# design.net
KiCad netlist of a schematic drawn in Altium Designer
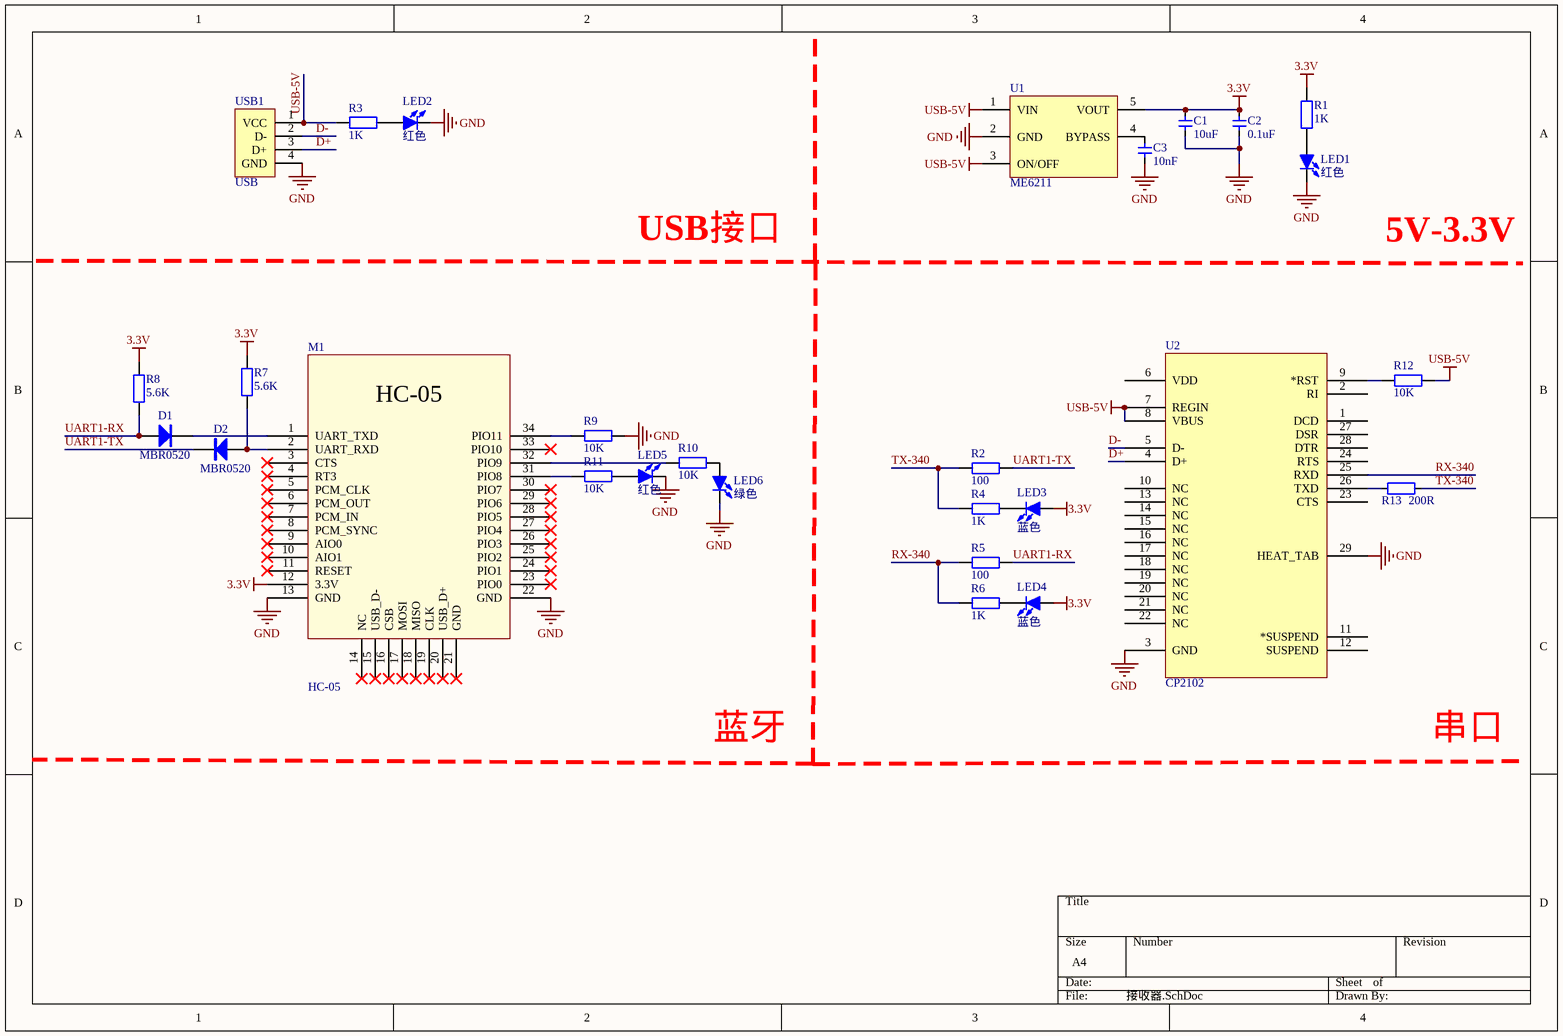
[diagram p0: 接收器.SchDoc]

(export (version "E")
  (design (tool "Eeschema 10.0.6"))
  (components
    (comp (ref "C1")
      (value "10uF")
      (footprint "C 0402_L")
      (description "Capacitor")
      (libsource (lib "MyPcbLib") (part "电容-0402"))
    )
    (comp (ref "C2")
      (value "0.1uF")
      (footprint "C 0402_L")
      (description "Capacitor")
      (libsource (lib "MyPcbLib") (part "电容-0402"))
    )
    (comp (ref "C3")
      (value "10nF")
      (footprint "C 0402_L")
      (description "Capacitor")
      (libsource (lib "MyPcbLib") (part "电容-0402"))
    )
    (comp (ref "D1")
      (value "MBR0520")
      (footprint "SOD-123")
      (description "整流二极管")
      (libsource (lib "0.2 -  二极管-整流桥") (part "1N4007"))
    )
    (comp (ref "D2")
      (value "MBR0520")
      (footprint "SOD-123")
      (description "整流二极管")
      (libsource (lib "0.2 -  二极管-整流桥") (part "1N4007"))
    )
    (comp (ref "LED1")
      (value "红色")
      (footprint "LED 0603R")
      (description "贴片LED")
      (fields (field (name "版权归属") "封装库来自淘宝 ID：黄晶宝石"))
      (libsource (lib "0.3 - LED发光二极管") (part "LED-SMD"))
    )
    (comp (ref "LED2")
      (value "红色")
      (footprint "LED 0603R")
      (description "贴片LED")
      (fields (field (name "版权归属") "封装库来自淘宝 ID：黄晶宝石"))
      (libsource (lib "0.3 - LED发光二极管") (part "LED-SMD"))
    )
    (comp (ref "LED3")
      (value "蓝色")
      (footprint "LED 0603B")
      (description "贴片LED")
      (fields (field (name "版权归属") "封装库来自淘宝 ID：黄晶宝石"))
      (libsource (lib "0.3 - LED发光二极管") (part "LED-SMD"))
    )
    (comp (ref "LED4")
      (value "蓝色")
      (footprint "LED 0603B")
      (description "贴片LED")
      (fields (field (name "版权归属") "封装库来自淘宝 ID：黄晶宝石"))
      (libsource (lib "0.3 - LED发光二极管") (part "LED-SMD"))
    )
    (comp (ref "LED5")
      (value "红色")
      (footprint "LED 0603R")
      (description "贴片LED")
      (fields (field (name "版权归属") "封装库来自淘宝 ID：黄晶宝石"))
      (libsource (lib "0.3 - LED发光二极管") (part "LED-SMD"))
    )
    (comp (ref "LED6")
      (value "绿色")
      (footprint "LED 0603G")
      (description "贴片LED")
      (fields (field (name "版权归属") "封装库来自淘宝 ID：黄晶宝石"))
      (libsource (lib "0.3 - LED发光二极管") (part "LED-SMD"))
    )
    (comp (ref "M1")
      (value "HC-05")
      (footprint "HC-05")
      (description "串口蓝牙模块")
      (fields (field (name "版权归属") "源创客"))
      (libsource (lib "模块") (part "HC-05"))
    )
    (comp (ref "R1")
      (value "1K")
      (footprint "R 0402_L")
      (description "贴片电阻")
      (fields (field (name "版权归属") "来自淘宝 ID：黄晶宝石"))
      (libsource (lib "0.1 - 电阻-电容-电感") (part "R"))
    )
    (comp (ref "R2")
      (value "100")
      (footprint "R 0402_L")
      (description "贴片电阻")
      (fields (field (name "版权归属") "来自淘宝 ID：黄晶宝石"))
      (libsource (lib "0.1 - 电阻-电容-电感") (part "R"))
    )
    (comp (ref "R3")
      (value "1K")
      (footprint "R 0402_L")
      (description "贴片电阻")
      (fields (field (name "版权归属") "来自淘宝 ID：黄晶宝石"))
      (libsource (lib "0.1 - 电阻-电容-电感") (part "R"))
    )
    (comp (ref "R4")
      (value "1K")
      (footprint "R 0402_L")
      (description "贴片电阻")
      (fields (field (name "版权归属") "来自淘宝 ID：黄晶宝石"))
      (libsource (lib "0.1 - 电阻-电容-电感") (part "R"))
    )
    (comp (ref "R5")
      (value "100")
      (footprint "R 0402_L")
      (description "贴片电阻")
      (fields (field (name "版权归属") "来自淘宝 ID：黄晶宝石"))
      (libsource (lib "0.1 - 电阻-电容-电感") (part "R"))
    )
    (comp (ref "R6")
      (value "1K")
      (footprint "R 0402_L")
      (description "贴片电阻")
      (fields (field (name "版权归属") "来自淘宝 ID：黄晶宝石"))
      (libsource (lib "0.1 - 电阻-电容-电感") (part "R"))
    )
    (comp (ref "R7")
      (value "5.6K")
      (footprint "R 0402_L")
      (description "贴片电阻")
      (fields (field (name "版权归属") "来自淘宝 ID：黄晶宝石"))
      (libsource (lib "0.1 - 电阻-电容-电感") (part "R"))
    )
    (comp (ref "R8")
      (value "5.6K")
      (footprint "R 0402_L")
      (description "贴片电阻")
      (fields (field (name "版权归属") "来自淘宝 ID：黄晶宝石"))
      (libsource (lib "0.1 - 电阻-电容-电感") (part "R"))
    )
    (comp (ref "R9")
      (value "10K")
      (footprint "R 0402_L")
      (description "贴片电阻")
      (fields (field (name "版权归属") "来自淘宝 ID：黄晶宝石"))
      (libsource (lib "0.1 - 电阻-电容-电感") (part "R"))
    )
    (comp (ref "R10")
      (value "10K")
      (footprint "R 0402_L")
      (description "贴片电阻")
      (fields (field (name "版权归属") "来自淘宝 ID：黄晶宝石"))
      (libsource (lib "0.1 - 电阻-电容-电感") (part "R"))
    )
    (comp (ref "R11")
      (value "10K")
      (footprint "R 0402_L")
      (description "贴片电阻")
      (fields (field (name "版权归属") "来自淘宝 ID：黄晶宝石"))
      (libsource (lib "0.1 - 电阻-电容-电感") (part "R"))
    )
    (comp (ref "R12")
      (value "10K")
      (footprint "R 0402_L")
      (description "贴片电阻")
      (fields (field (name "版权归属") "来自淘宝 ID：黄晶宝石"))
      (libsource (lib "0.1 - 电阻-电容-电感") (part "R"))
    )
    (comp (ref "R13")
      (value "200R")
      (footprint "R 0402_L")
      (description "Resistor")
      (libsource (lib "MyPcbLib") (part "电阻-0402"))
    )
    (comp (ref "U1")
      (value "ME6211")
      (footprint "SOT23-5")
      (description "DC降压芯片")
      (libsource (lib "1.1 - 电源类芯片") (part "ME6211"))
    )
    (comp (ref "U2")
      (value "CP2102")
      (footprint "QFN-28")
      (description "USB转TTL")
      (libsource (lib "mLib") (part "CP2102"))
    )
    (comp (ref "USB1")
      (value "USB")
      (footprint "USB_A/P_A")
      (description "USB-A型公接口")
      (fields (field (name "版权归属") "源创客"))
      (libsource (lib "接口类") (part "USB-A/P"))
    )
  )
  (nets
    (net (code "1") (name "/D+") (class "Default")
      (node (ref "U2") (pin "4") (pinfunction "D+_4") (pintype "passive"))
      (node (ref "USB1") (pin "3") (pinfunction "D+_3") (pintype "passive"))
    )
    (net (code "2") (name "/D-") (class "Default")
      (node (ref "U2") (pin "5") (pinfunction "D-_5") (pintype "passive"))
      (node (ref "USB1") (pin "2") (pinfunction "D-_2") (pintype "passive"))
    )
    (net (code "3") (name "/RX-340") (class "Default")
      (node (ref "R5") (pin "1") (pinfunction "1_1") (pintype "passive"))
      (node (ref "R6") (pin "1") (pinfunction "1_1") (pintype "passive"))
      (node (ref "U2") (pin "25") (pinfunction "RXD_25") (pintype "passive"))
    )
    (net (code "4") (name "/TX-340") (class "Default")
      (node (ref "R13") (pin "1") (pinfunction "1_1") (pintype "passive"))
      (node (ref "R2") (pin "1") (pinfunction "1_1") (pintype "passive"))
      (node (ref "R4") (pin "1") (pinfunction "1_1") (pintype "passive"))
    )
    (net (code "5") (name "/UART1-RX") (class "Default")
      (node (ref "D1") (pin "1") (pinfunction "A_1") (pintype "passive"))
      (node (ref "R5") (pin "2") (pinfunction "2_2") (pintype "passive"))
      (node (ref "R8") (pin "1") (pinfunction "1_1") (pintype "passive"))
    )
    (net (code "6") (name "/UART1-TX") (class "Default")
      (node (ref "D2") (pin "2") (pinfunction "K_2") (pintype "passive"))
      (node (ref "R2") (pin "2") (pinfunction "2_2") (pintype "passive"))
    )
    (net (code "7") (name "3.3V") (class "Default")
      (node (ref "C1") (pin "2") (pinfunction "2_2") (pintype "passive"))
      (node (ref "C2") (pin "2") (pinfunction "2_2") (pintype "passive"))
      (node (ref "LED3") (pin "1") (pinfunction "A_1") (pintype "passive"))
      (node (ref "LED4") (pin "1") (pinfunction "A_1") (pintype "passive"))
      (node (ref "M1") (pin "12") (pinfunction "3.3V_12") (pintype "passive"))
      (node (ref "R1") (pin "2") (pinfunction "2_2") (pintype "passive"))
      (node (ref "R7") (pin "2") (pinfunction "2_2") (pintype "passive"))
      (node (ref "R8") (pin "2") (pinfunction "2_2") (pintype "passive"))
      (node (ref "U1") (pin "5") (pinfunction "VOUT_5") (pintype "passive"))
    )
    (net (code "8") (name "GND") (class "Default")
      (node (ref "C1") (pin "1") (pinfunction "1_1") (pintype "passive"))
      (node (ref "C2") (pin "1") (pinfunction "1_1") (pintype "passive"))
      (node (ref "C3") (pin "1") (pinfunction "1_1") (pintype "passive"))
      (node (ref "LED1") (pin "2") (pinfunction "K_2") (pintype "passive"))
      (node (ref "LED2") (pin "2") (pinfunction "K_2") (pintype "passive"))
      (node (ref "LED5") (pin "2") (pinfunction "K_2") (pintype "passive"))
      (node (ref "LED6") (pin "2") (pinfunction "K_2") (pintype "passive"))
      (node (ref "M1") (pin "13") (pinfunction "GND_13") (pintype "passive"))
      (node (ref "M1") (pin "22") (pinfunction "GND_22") (pintype "passive"))
      (node (ref "R9") (pin "2") (pinfunction "2_2") (pintype "passive"))
      (node (ref "U1") (pin "2") (pinfunction "GND_2") (pintype "passive"))
      (node (ref "U2") (pin "29") (pinfunction "HEAT_TAB_29") (pintype "passive"))
      (node (ref "U2") (pin "3") (pinfunction "GND_3") (pintype "passive"))
      (node (ref "USB1") (pin "4") (pinfunction "GND_4") (pintype "passive"))
    )
    (net (code "9") (name "Net-(D1-K)") (class "Default")
      (node (ref "D1") (pin "2") (pinfunction "K_2") (pintype "passive"))
      (node (ref "M1") (pin "1") (pinfunction "UART_TXD_1") (pintype "passive"))
    )
    (net (code "10") (name "Net-(D2-A)") (class "Default")
      (node (ref "D2") (pin "1") (pinfunction "A_1") (pintype "passive"))
      (node (ref "M1") (pin "2") (pinfunction "UART_RXD_2") (pintype "passive"))
      (node (ref "R7") (pin "1") (pinfunction "1_1") (pintype "passive"))
    )
    (net (code "11") (name "Net-(LED1-A)") (class "Default")
      (node (ref "LED1") (pin "1") (pinfunction "A_1") (pintype "passive"))
      (node (ref "R1") (pin "1") (pinfunction "1_1") (pintype "passive"))
    )
    (net (code "12") (name "Net-(LED2-A)") (class "Default")
      (node (ref "LED2") (pin "1") (pinfunction "A_1") (pintype "passive"))
      (node (ref "R3") (pin "1") (pinfunction "1_1") (pintype "passive"))
    )
    (net (code "13") (name "Net-(LED3-K)") (class "Default")
      (node (ref "LED3") (pin "2") (pinfunction "K_2") (pintype "passive"))
      (node (ref "R4") (pin "2") (pinfunction "2_2") (pintype "passive"))
    )
    (net (code "14") (name "Net-(LED4-K)") (class "Default")
      (node (ref "LED4") (pin "2") (pinfunction "K_2") (pintype "passive"))
      (node (ref "R6") (pin "2") (pinfunction "2_2") (pintype "passive"))
    )
    (net (code "15") (name "Net-(LED5-A)") (class "Default")
      (node (ref "LED5") (pin "1") (pinfunction "A_1") (pintype "passive"))
      (node (ref "R11") (pin "2") (pinfunction "2_2") (pintype "passive"))
    )
    (net (code "16") (name "Net-(LED6-A)") (class "Default")
      (node (ref "LED6") (pin "1") (pinfunction "A_1") (pintype "passive"))
      (node (ref "R10") (pin "2") (pinfunction "2_2") (pintype "passive"))
    )
    (net (code "17") (name "Net-(M1-PIO8)") (class "Default")
      (node (ref "M1") (pin "31") (pinfunction "PIO8_31") (pintype "passive"))
      (node (ref "R11") (pin "1") (pinfunction "1_1") (pintype "passive"))
    )
    (net (code "18") (name "Net-(M1-PIO9)") (class "Default")
      (node (ref "M1") (pin "32") (pinfunction "PIO9_32") (pintype "passive"))
      (node (ref "R10") (pin "1") (pinfunction "1_1") (pintype "passive"))
    )
    (net (code "19") (name "Net-(M1-PIO11)") (class "Default")
      (node (ref "M1") (pin "34") (pinfunction "PIO11_34") (pintype "passive"))
      (node (ref "R9") (pin "1") (pinfunction "1_1") (pintype "passive"))
    )
    (net (code "20") (name "Net-(U1-BYPASS)") (class "Default")
      (node (ref "C3") (pin "2") (pinfunction "2_2") (pintype "passive"))
      (node (ref "U1") (pin "4") (pinfunction "BYPASS_4") (pintype "passive"))
    )
    (net (code "21") (name "Net-(U2-*RST)") (class "Default")
      (node (ref "R12") (pin "2") (pinfunction "2_2") (pintype "passive"))
      (node (ref "U2") (pin "9") (pinfunction "*RST_9") (pintype "passive"))
    )
    (net (code "22") (name "Net-(U2-TXD)") (class "Default")
      (node (ref "R13") (pin "2") (pinfunction "2_2") (pintype "passive"))
      (node (ref "U2") (pin "26") (pinfunction "TXD_26") (pintype "passive"))
    )
    (net (code "23") (name "USB-5V") (class "Default")
      (node (ref "R12") (pin "1") (pinfunction "1_1") (pintype "passive"))
      (node (ref "R3") (pin "2") (pinfunction "2_2") (pintype "passive"))
      (node (ref "U1") (pin "1") (pinfunction "VIN_1") (pintype "passive"))
      (node (ref "U1") (pin "3") (pinfunction "ON/OFF_3") (pintype "passive"))
      (node (ref "U2") (pin "7") (pinfunction "REGIN_7") (pintype "passive"))
      (node (ref "U2") (pin "8") (pinfunction "VBUS_8") (pintype "passive"))
      (node (ref "USB1") (pin "1") (pinfunction "VCC_1") (pintype "passive"))
    )
    (net (code "24") (name "unconnected-(M1-AIO0-Pad9)") (class "Default")
      (node (ref "M1") (pin "9") (pinfunction "AIO0_9") (pintype "passive+no_connect"))
    )
    (net (code "25") (name "unconnected-(M1-AIO1-Pad10)") (class "Default")
      (node (ref "M1") (pin "10") (pinfunction "AIO1_10") (pintype "passive+no_connect"))
    )
    (net (code "26") (name "unconnected-(M1-CLK-Pad19)") (class "Default")
      (node (ref "M1") (pin "19") (pinfunction "CLK_19") (pintype "passive+no_connect"))
    )
    (net (code "27") (name "unconnected-(M1-CSB-Pad16)") (class "Default")
      (node (ref "M1") (pin "16") (pinfunction "CSB_16") (pintype "passive+no_connect"))
    )
    (net (code "28") (name "unconnected-(M1-CTS-Pad3)") (class "Default")
      (node (ref "M1") (pin "3") (pinfunction "CTS_3") (pintype "passive+no_connect"))
    )
    (net (code "29") (name "unconnected-(M1-GND-Pad21)") (class "Default")
      (node (ref "M1") (pin "21") (pinfunction "GND_21") (pintype "passive+no_connect"))
    )
    (net (code "30") (name "unconnected-(M1-MISO-Pad18)") (class "Default")
      (node (ref "M1") (pin "18") (pinfunction "MISO_18") (pintype "passive+no_connect"))
    )
    (net (code "31") (name "unconnected-(M1-MOSI-Pad17)") (class "Default")
      (node (ref "M1") (pin "17") (pinfunction "MOSI_17") (pintype "passive+no_connect"))
    )
    (net (code "32") (name "unconnected-(M1-NC-Pad14)") (class "Default")
      (node (ref "M1") (pin "14") (pinfunction "NC_14") (pintype "passive+no_connect"))
    )
    (net (code "33") (name "unconnected-(M1-PCM_CLK-Pad5)") (class "Default")
      (node (ref "M1") (pin "5") (pinfunction "PCM_CLK_5") (pintype "passive+no_connect"))
    )
    (net (code "34") (name "unconnected-(M1-PCM_IN-Pad7)") (class "Default")
      (node (ref "M1") (pin "7") (pinfunction "PCM_IN_7") (pintype "passive+no_connect"))
    )
    (net (code "35") (name "unconnected-(M1-PCM_OUT-Pad6)") (class "Default")
      (node (ref "M1") (pin "6") (pinfunction "PCM_OUT_6") (pintype "passive+no_connect"))
    )
    (net (code "36") (name "unconnected-(M1-PCM_SYNC-Pad8)") (class "Default")
      (node (ref "M1") (pin "8") (pinfunction "PCM_SYNC_8") (pintype "passive+no_connect"))
    )
    (net (code "37") (name "unconnected-(M1-PIO0-Pad23)") (class "Default")
      (node (ref "M1") (pin "23") (pinfunction "PIO0_23") (pintype "passive+no_connect"))
    )
    (net (code "38") (name "unconnected-(M1-PIO1-Pad24)") (class "Default")
      (node (ref "M1") (pin "24") (pinfunction "PIO1_24") (pintype "passive+no_connect"))
    )
    (net (code "39") (name "unconnected-(M1-PIO2-Pad25)") (class "Default")
      (node (ref "M1") (pin "25") (pinfunction "PIO2_25") (pintype "passive+no_connect"))
    )
    (net (code "40") (name "unconnected-(M1-PIO3-Pad26)") (class "Default")
      (node (ref "M1") (pin "26") (pinfunction "PIO3_26") (pintype "passive+no_connect"))
    )
    (net (code "41") (name "unconnected-(M1-PIO4-Pad27)") (class "Default")
      (node (ref "M1") (pin "27") (pinfunction "PIO4_27") (pintype "passive+no_connect"))
    )
    (net (code "42") (name "unconnected-(M1-PIO5-Pad28)") (class "Default")
      (node (ref "M1") (pin "28") (pinfunction "PIO5_28") (pintype "passive+no_connect"))
    )
    (net (code "43") (name "unconnected-(M1-PIO6-Pad29)") (class "Default")
      (node (ref "M1") (pin "29") (pinfunction "PIO6_29") (pintype "passive+no_connect"))
    )
    (net (code "44") (name "unconnected-(M1-PIO7-Pad30)") (class "Default")
      (node (ref "M1") (pin "30") (pinfunction "PIO7_30") (pintype "passive+no_connect"))
    )
    (net (code "45") (name "unconnected-(M1-PIO10-Pad33)") (class "Default")
      (node (ref "M1") (pin "33") (pinfunction "PIO10_33") (pintype "passive+no_connect"))
    )
    (net (code "46") (name "unconnected-(M1-RESET-Pad11)") (class "Default")
      (node (ref "M1") (pin "11") (pinfunction "RESET_11") (pintype "passive+no_connect"))
    )
    (net (code "47") (name "unconnected-(M1-RT3-Pad4)") (class "Default")
      (node (ref "M1") (pin "4") (pinfunction "RT3_4") (pintype "passive+no_connect"))
    )
    (net (code "48") (name "unconnected-(M1-USB_D+-Pad20)") (class "Default")
      (node (ref "M1") (pin "20") (pinfunction "USB_D+_20") (pintype "passive+no_connect"))
    )
    (net (code "49") (name "unconnected-(M1-USB_D--Pad15)") (class "Default")
      (node (ref "M1") (pin "15") (pinfunction "USB_D-_15") (pintype "passive+no_connect"))
    )
    (net (code "50") (name "unconnected-(U2-*SUSPEND-Pad11)") (class "Default")
      (node (ref "U2") (pin "11") (pinfunction "*SUSPEND_11") (pintype "passive"))
    )
    (net (code "51") (name "unconnected-(U2-CTS-Pad23)") (class "Default")
      (node (ref "U2") (pin "23") (pinfunction "CTS_23") (pintype "passive"))
    )
    (net (code "52") (name "unconnected-(U2-DCD-Pad1)") (class "Default")
      (node (ref "U2") (pin "1") (pinfunction "DCD_1") (pintype "passive"))
    )
    (net (code "53") (name "unconnected-(U2-DSR-Pad27)") (class "Default")
      (node (ref "U2") (pin "27") (pinfunction "DSR_27") (pintype "passive"))
    )
    (net (code "54") (name "unconnected-(U2-DTR-Pad28)") (class "Default")
      (node (ref "U2") (pin "28") (pinfunction "DTR_28") (pintype "passive"))
    )
    (net (code "55") (name "unconnected-(U2-NC-Pad10)") (class "Default")
      (node (ref "U2") (pin "10") (pinfunction "NC_10") (pintype "passive"))
    )
    (net (code "56") (name "unconnected-(U2-NC-Pad13)") (class "Default")
      (node (ref "U2") (pin "13") (pinfunction "NC_13") (pintype "passive"))
    )
    (net (code "57") (name "unconnected-(U2-NC-Pad14)") (class "Default")
      (node (ref "U2") (pin "14") (pinfunction "NC_14") (pintype "passive"))
    )
    (net (code "58") (name "unconnected-(U2-NC-Pad15)") (class "Default")
      (node (ref "U2") (pin "15") (pinfunction "NC_15") (pintype "passive"))
    )
    (net (code "59") (name "unconnected-(U2-NC-Pad16)") (class "Default")
      (node (ref "U2") (pin "16") (pinfunction "NC_16") (pintype "passive"))
    )
    (net (code "60") (name "unconnected-(U2-NC-Pad17)") (class "Default")
      (node (ref "U2") (pin "17") (pinfunction "NC_17") (pintype "passive"))
    )
    (net (code "61") (name "unconnected-(U2-NC-Pad18)") (class "Default")
      (node (ref "U2") (pin "18") (pinfunction "NC_18") (pintype "passive"))
    )
    (net (code "62") (name "unconnected-(U2-NC-Pad19)") (class "Default")
      (node (ref "U2") (pin "19") (pinfunction "NC_19") (pintype "passive"))
    )
    (net (code "63") (name "unconnected-(U2-NC-Pad20)") (class "Default")
      (node (ref "U2") (pin "20") (pinfunction "NC_20") (pintype "passive"))
    )
    (net (code "64") (name "unconnected-(U2-NC-Pad21)") (class "Default")
      (node (ref "U2") (pin "21") (pinfunction "NC_21") (pintype "passive"))
    )
    (net (code "65") (name "unconnected-(U2-NC-Pad22)") (class "Default")
      (node (ref "U2") (pin "22") (pinfunction "NC_22") (pintype "passive"))
    )
    (net (code "66") (name "unconnected-(U2-RI-Pad2)") (class "Default")
      (node (ref "U2") (pin "2") (pinfunction "RI_2") (pintype "passive"))
    )
    (net (code "67") (name "unconnected-(U2-RTS-Pad24)") (class "Default")
      (node (ref "U2") (pin "24") (pinfunction "RTS_24") (pintype "passive"))
    )
    (net (code "68") (name "unconnected-(U2-SUSPEND-Pad12)") (class "Default")
      (node (ref "U2") (pin "12") (pinfunction "SUSPEND_12") (pintype "passive"))
    )
    (net (code "69") (name "unconnected-(U2-VDD-Pad6)") (class "Default")
      (node (ref "U2") (pin "6") (pinfunction "VDD_6") (pintype "passive"))
    )
  )
)
